# RF_Power_small_doubler.net
KiCad netlist of a schematic drawn in Altium Designer
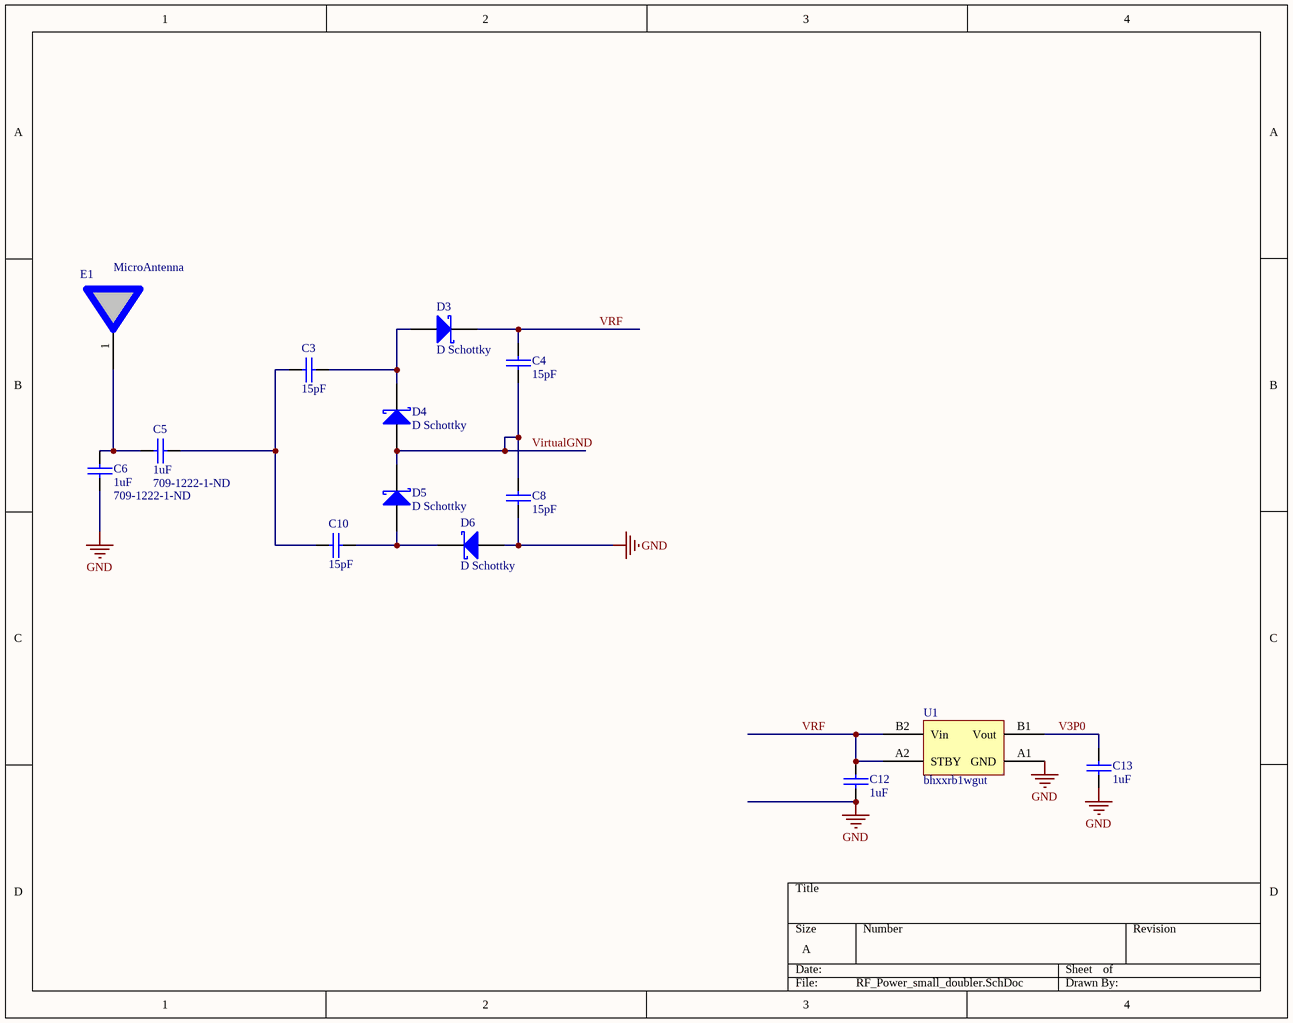
[diagram p0: RF_Power_small_doubler.SchDoc]

(export (version "E")
  (design (tool "Eeschema 10.0.6"))
  (components
    (comp (ref "C3")
      (value "15pF")
      (footprint "0201")
      (description "Capacitor")
      (fields (field (name "Comment") "NP0 50V"))
      (libsource (lib "nRF24LE1F16Q24") (part "Cap"))
    )
    (comp (ref "C4")
      (value "15pF")
      (footprint "0201")
      (description "Capacitor")
      (fields (field (name "Comment") "NP0 50V"))
      (libsource (lib "nRF24LE1F16Q24") (part "Cap"))
    )
    (comp (ref "C5")
      (value "1uF")
      (footprint "0402")
      (description "Capacitor")
      (fields
        (field (name "SUPPLIER PART NUMBER 1") "709-1222-1-ND")
        (field (name "MANUFACTURER") "Johanson Dielectrics Inc")
        (field (name "MANUFACTURER PART NUMBER") "100R07X105KV4T")
      )
      (libsource (lib "nRF24LE1F16Q24") (part "Cap"))
    )
    (comp (ref "C6")
      (value "1uF")
      (footprint "0402")
      (description "Capacitor")
      (fields
        (field (name "SUPPLIER PART NUMBER 1") "709-1222-1-ND")
        (field (name "MANUFACTURER") "Johanson Dielectrics Inc")
        (field (name "MANUFACTURER PART NUMBER") "100R07X105KV4T")
      )
      (libsource (lib "nRF24LE1F16Q24") (part "Cap"))
    )
    (comp (ref "C8")
      (value "15pF")
      (footprint "0201")
      (description "Capacitor")
      (fields (field (name "Comment") "NP0 50V"))
      (libsource (lib "nRF24LE1F16Q24") (part "Cap"))
    )
    (comp (ref "C10")
      (value "15pF")
      (footprint "0201")
      (description "Capacitor")
      (fields (field (name "Comment") "NP0 50V"))
      (libsource (lib "nRF24LE1F16Q24") (part "Cap"))
    )
    (comp (ref "C12")
      (value "1uF")
      (footprint "CAPC1005L")
      (description "Capacitor")
      (fields (field (name "Comment") "NP0 50V"))
      (libsource (lib "nRF24LE1F16Q24") (part "Cap"))
    )
    (comp (ref "C13")
      (value "1uF")
      (footprint "CAPC1005L")
      (description "Capacitor")
      (fields (field (name "Comment") "NP0 50V"))
      (libsource (lib "nRF24LE1F16Q24") (part "Cap"))
    )
    (comp (ref "D3")
      (value "D Schottky")
      (footprint "Diode0201")
      (description "Schottky Diode")
      (fields (field (name "PUBLISHER") "Altium Limited"))
      (libsource (lib "Miscellaneous Devices") (part "D Schottky"))
    )
    (comp (ref "D4")
      (value "D Schottky")
      (footprint "Diode0201")
      (description "Schottky Diode")
      (fields (field (name "PUBLISHER") "Altium Limited"))
      (libsource (lib "Miscellaneous Devices") (part "D Schottky"))
    )
    (comp (ref "D5")
      (value "D Schottky")
      (footprint "Diode0201")
      (description "Schottky Diode")
      (fields (field (name "PUBLISHER") "Altium Limited"))
      (libsource (lib "Miscellaneous Devices") (part "D Schottky"))
    )
    (comp (ref "D6")
      (value "D Schottky")
      (footprint "Diode0201")
      (description "Schottky Diode")
      (fields (field (name "PUBLISHER") "Altium Limited"))
      (libsource (lib "Miscellaneous Devices") (part "D Schottky"))
    )
    (comp (ref "E1")
      (value "MicroAntenna")
      (footprint "2450AT18B100")
      (libsource (lib "custom") (part "MicroAntenna"))
    )
    (comp (ref "U1")
      (value "bhxxrb1wgut")
      (footprint "BGA2x2_p5")
      (libsource (lib "custom") (part "bhxxrb1wgut"))
    )
  )
  (nets
    (net (code "1") (name "/V3P0") (class "Default")
      (node (ref "C13") (pin "2") (pintype "passive"))
      (node (ref "U1") (pin "B1") (pinfunction "Vout_B1") (pintype "passive"))
    )
    (net (code "2") (name "/VRF") (class "Default")
      (node (ref "C12") (pin "1") (pintype "passive"))
      (node (ref "C4") (pin "1") (pintype "passive"))
      (node (ref "D3") (pin "2") (pinfunction "K_2") (pintype "passive"))
      (node (ref "U1") (pin "A2") (pinfunction "STBY_A2") (pintype "passive"))
      (node (ref "U1") (pin "B2") (pinfunction "Vin_B2") (pintype "passive"))
    )
    (net (code "3") (name "/VirtualGND") (class "Default")
      (node (ref "C4") (pin "2") (pintype "passive"))
      (node (ref "C8") (pin "1") (pintype "passive"))
      (node (ref "D4") (pin "1") (pinfunction "A_1") (pintype "passive"))
      (node (ref "D5") (pin "2") (pinfunction "K_2") (pintype "passive"))
    )
    (net (code "4") (name "GND") (class "Default")
      (node (ref "C12") (pin "2") (pintype "passive"))
      (node (ref "C13") (pin "1") (pintype "passive"))
      (node (ref "C6") (pin "2") (pintype "passive"))
      (node (ref "C8") (pin "2") (pintype "passive"))
      (node (ref "D6") (pin "1") (pinfunction "A_1") (pintype "passive"))
      (node (ref "U1") (pin "A1") (pinfunction "GND_A1") (pintype "passive"))
    )
    (net (code "5") (name "Net-(C5-Pad2)") (class "Default")
      (node (ref "C5") (pin "2") (pintype "passive"))
      (node (ref "C6") (pin "1") (pintype "passive"))
      (node (ref "E1") (pin "1") (pinfunction "1_1") (pintype "passive"))
    )
    (net (code "6") (name "Net-(C10-Pad2)") (class "Default")
      (node (ref "C10") (pin "2") (pintype "passive"))
      (node (ref "C3") (pin "2") (pintype "passive"))
      (node (ref "C5") (pin "1") (pintype "passive"))
    )
    (net (code "7") (name "Net-(D3-A)") (class "Default")
      (node (ref "C3") (pin "1") (pintype "passive"))
      (node (ref "D3") (pin "1") (pinfunction "A_1") (pintype "passive"))
      (node (ref "D4") (pin "2") (pinfunction "K_2") (pintype "passive"))
    )
    (net (code "8") (name "Net-(D5-A)") (class "Default")
      (node (ref "C10") (pin "1") (pintype "passive"))
      (node (ref "D5") (pin "1") (pinfunction "A_1") (pintype "passive"))
      (node (ref "D6") (pin "2") (pinfunction "K_2") (pintype "passive"))
    )
    (net (code "9") (name "unconnected-(E1-Pad2)") (class "Default")
      (node (ref "E1") (pin "2") (pinfunction "2_2") (pintype "passive"))
    )
  )
)
